# mosfet-cs.net
KiCad netlist of a schematic drawn in EAGLE
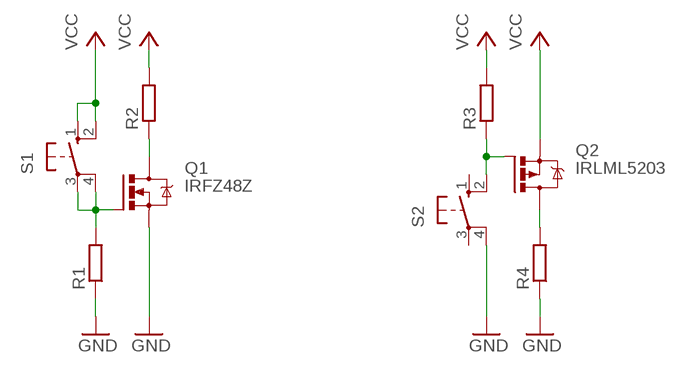
[diagram p0: schematic, sheet 1]

(export (version "E")
  (design (tool "Eeschema 10.0.6"))
  (components
    (comp (ref "Q1")
      (value "IRFZ48Z")
      (footprint "eagle-import:TO220BH")
      (libsource (lib "eagle-import") (part "IRFZ48Z"))
    )
    (comp (ref "Q2")
      (value "IRLML5203")
      (footprint "eagle-import:MICRO3")
      (libsource (lib "eagle-import") (part "IRLML5203"))
    )
    (comp (ref "R1")
      (value "R-EU_0207/10")
      (footprint "eagle-import:0207_10")
      (libsource (lib "eagle-import") (part "R-EU_0207/10"))
    )
    (comp (ref "R2")
      (value "R-EU_0207/10")
      (footprint "eagle-import:0207_10")
      (libsource (lib "eagle-import") (part "R-EU_0207/10"))
    )
    (comp (ref "R3")
      (value "R-EU_0207/10")
      (footprint "eagle-import:0207_10")
      (libsource (lib "eagle-import") (part "R-EU_0207/10"))
    )
    (comp (ref "R4")
      (value "R-EU_0207/10")
      (footprint "eagle-import:0207_10")
      (libsource (lib "eagle-import") (part "R-EU_0207/10"))
    )
    (comp (ref "S1")
      (value "10-XX")
      (footprint "eagle-import:B3F-10XX")
      (fields (field (name "MPN") "B3F-1000"))
      (libsource (lib "eagle-import") (part "10-XX"))
    )
    (comp (ref "S2")
      (value "10-XX")
      (footprint "eagle-import:B3F-10XX")
      (fields (field (name "MPN") "B3F-1000"))
      (libsource (lib "eagle-import") (part "10-XX"))
    )
  )
  (nets
    (net (code "1") (name "GND") (class "Default")
      (node (ref "Q1") (pin "S") (pinfunction "S_S") (pintype "passive"))
      (node (ref "R1") (pin "1") (pinfunction "1_1") (pintype "passive"))
      (node (ref "R4") (pin "1") (pinfunction "1_1") (pintype "passive"))
      (node (ref "S2") (pin "4") (pinfunction "P1_4") (pintype "passive"))
    )
    (net (code "2") (name "Net-(Q1-PadD)") (class "Default")
      (node (ref "Q1") (pin "D") (pinfunction "D_D") (pintype "passive"))
      (node (ref "R2") (pin "1") (pinfunction "1_1") (pintype "passive"))
    )
    (net (code "3") (name "Net-(Q2-D)") (class "Default")
      (node (ref "Q2") (pin "3") (pinfunction "D_3") (pintype "passive"))
      (node (ref "R4") (pin "2") (pinfunction "2_2") (pintype "passive"))
    )
    (net (code "4") (name "Net-(Q2-G)") (class "Default")
      (node (ref "Q2") (pin "1") (pinfunction "G_1") (pintype "passive"))
      (node (ref "R3") (pin "1") (pinfunction "1_1") (pintype "passive"))
      (node (ref "S2") (pin "2") (pinfunction "S1_2") (pintype "passive"))
    )
    (net (code "5") (name "Net-(S1-P)") (class "Default")
      (node (ref "Q1") (pin "G") (pinfunction "G_G") (pintype "passive"))
      (node (ref "R1") (pin "2") (pinfunction "2_2") (pintype "passive"))
      (node (ref "S1") (pin "3") (pinfunction "P_3") (pintype "passive"))
      (node (ref "S1") (pin "4") (pinfunction "P1_4") (pintype "passive"))
    )
    (net (code "6") (name "VCC") (class "Default")
      (node (ref "Q2") (pin "2") (pinfunction "S_2") (pintype "passive"))
      (node (ref "R2") (pin "2") (pinfunction "2_2") (pintype "passive"))
      (node (ref "R3") (pin "2") (pinfunction "2_2") (pintype "passive"))
      (node (ref "S1") (pin "1") (pinfunction "S_1") (pintype "passive"))
      (node (ref "S1") (pin "2") (pinfunction "S1_2") (pintype "passive"))
    )
    (net (code "7") (name "unconnected-(S2-P-Pad3)") (class "Default")
      (node (ref "S2") (pin "3") (pinfunction "P_3") (pintype "passive"))
    )
    (net (code "8") (name "unconnected-(S2-S-Pad1)") (class "Default")
      (node (ref "S2") (pin "1") (pinfunction "S_1") (pintype "passive"))
    )
  )
)
